# v0_2_4ch.net
KiCad netlist of a schematic drawn in EAGLE
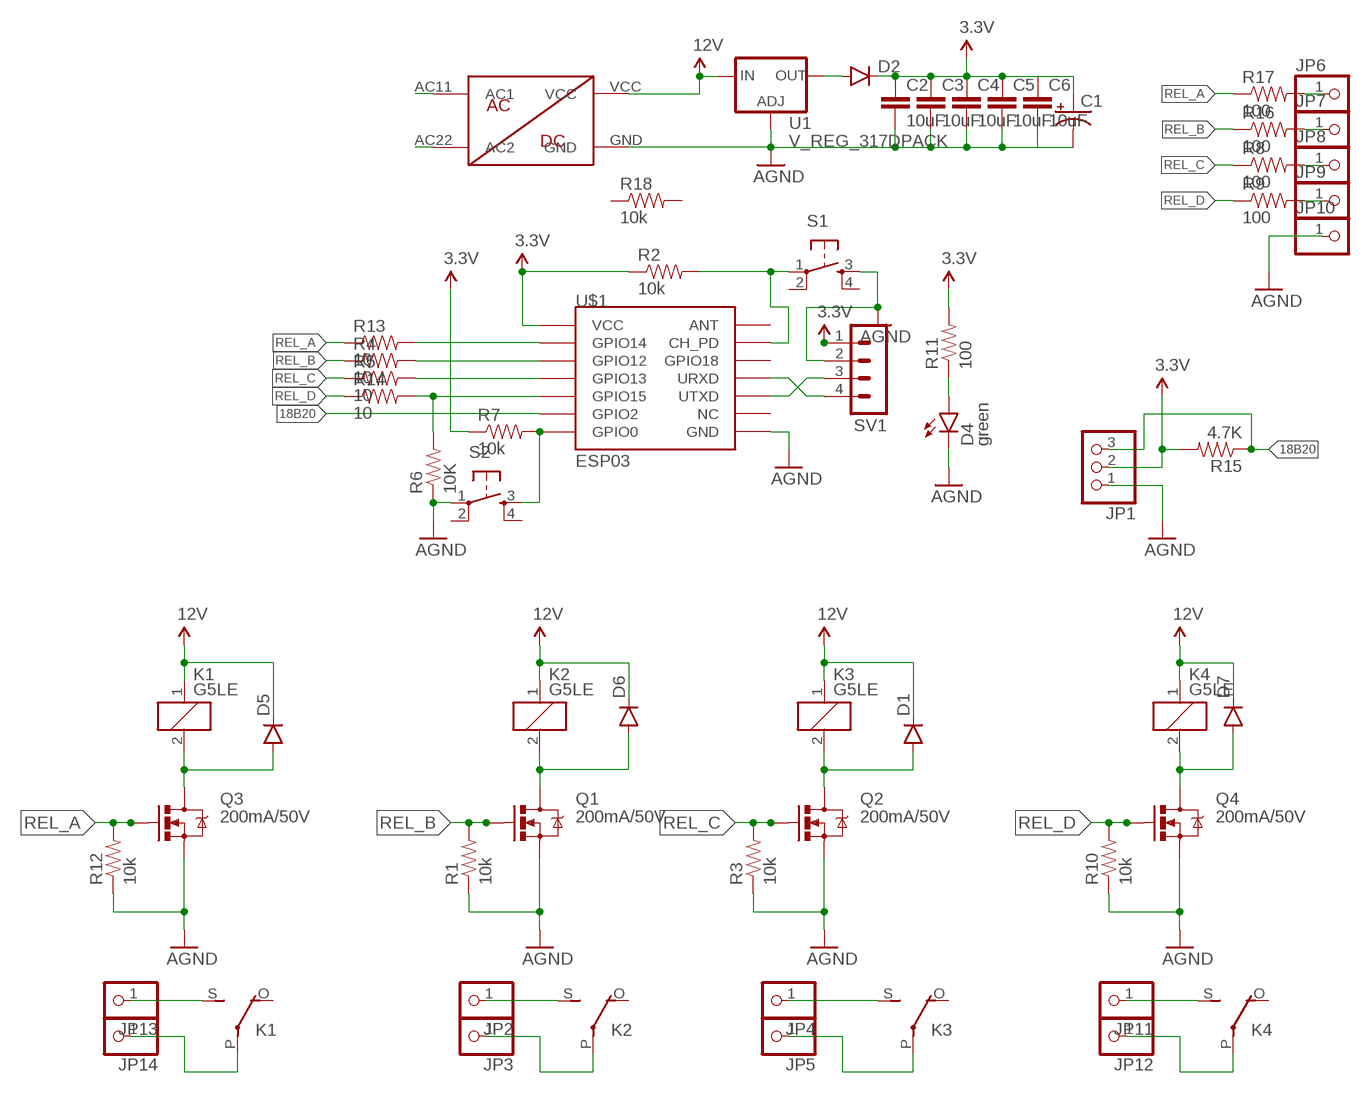
[diagram p0: schematic, sheet 1]

(export (version "E")
  (design (tool "Eeschema 10.0.6"))
  (components
    (comp (ref "C1")
      (value "CAP_POLPTH3")
      (footprint "eagle-import:CPOL-RADIAL-1000UF-63V")
      (libsource (lib "eagle-import") (part "CAP_POLPTH3"))
    )
    (comp (ref "C2")
      (value "10uF")
      (footprint "eagle-import:0603-CAP")
      (libsource (lib "eagle-import") (part "10UF-6.3V-20%(0603)"))
    )
    (comp (ref "C3")
      (value "10uF")
      (footprint "eagle-import:0603-CAP")
      (libsource (lib "eagle-import") (part "10UF-6.3V-20%(0603)"))
    )
    (comp (ref "C4")
      (value "10uF")
      (footprint "eagle-import:0603-CAP")
      (libsource (lib "eagle-import") (part "10UF-6.3V-20%(0603)"))
    )
    (comp (ref "C5")
      (value "10uF")
      (footprint "eagle-import:0603-CAP")
      (libsource (lib "eagle-import") (part "10UF-6.3V-20%(0603)"))
    )
    (comp (ref "C6")
      (value "10uF")
      (footprint "eagle-import:0603-CAP")
      (libsource (lib "eagle-import") (part "10UF-6.3V-20%(0603)"))
    )
    (comp (ref "D1")
      (value "DIODESOD123")
      (footprint "eagle-import:SOD-123")
      (libsource (lib "eagle-import") (part "DIODESOD123"))
    )
    (comp (ref "D2")
      (value "DIODESOD123")
      (footprint "eagle-import:SOD-123")
      (libsource (lib "eagle-import") (part "DIODESOD123"))
    )
    (comp (ref "D4")
      (value "green")
      (footprint "eagle-import:LED-0603")
      (libsource (lib "eagle-import") (part "LED0603"))
    )
    (comp (ref "D5")
      (value "DIODESOD123")
      (footprint "eagle-import:SOD-123")
      (libsource (lib "eagle-import") (part "DIODESOD123"))
    )
    (comp (ref "D6")
      (value "DIODESOD123")
      (footprint "eagle-import:SOD-123")
      (libsource (lib "eagle-import") (part "DIODESOD123"))
    )
    (comp (ref "D7")
      (value "DIODESOD123")
      (footprint "eagle-import:SOD-123")
      (libsource (lib "eagle-import") (part "DIODESOD123"))
    )
    (comp (ref "JP1")
      (value "PINHD-1X3")
      (footprint "eagle-import:1X03")
      (libsource (lib "eagle-import") (part "PINHD-1X3"))
    )
    (comp (ref "JP2")
      (value "PINHD-1X1")
      (footprint "eagle-import:1X01")
      (libsource (lib "eagle-import") (part "PINHD-1X1"))
    )
    (comp (ref "JP3")
      (value "PINHD-1X1")
      (footprint "eagle-import:1X01")
      (libsource (lib "eagle-import") (part "PINHD-1X1"))
    )
    (comp (ref "JP4")
      (value "PINHD-1X1")
      (footprint "eagle-import:1X01")
      (libsource (lib "eagle-import") (part "PINHD-1X1"))
    )
    (comp (ref "JP5")
      (value "PINHD-1X1")
      (footprint "eagle-import:1X01")
      (libsource (lib "eagle-import") (part "PINHD-1X1"))
    )
    (comp (ref "JP6")
      (value "PINHD-1X1")
      (footprint "eagle-import:1X01")
      (libsource (lib "eagle-import") (part "PINHD-1X1"))
    )
    (comp (ref "JP7")
      (value "PINHD-1X1")
      (footprint "eagle-import:1X01")
      (libsource (lib "eagle-import") (part "PINHD-1X1"))
    )
    (comp (ref "JP8")
      (value "PINHD-1X1")
      (footprint "eagle-import:1X01")
      (libsource (lib "eagle-import") (part "PINHD-1X1"))
    )
    (comp (ref "JP9")
      (value "PINHD-1X1")
      (footprint "eagle-import:1X01")
      (libsource (lib "eagle-import") (part "PINHD-1X1"))
    )
    (comp (ref "JP10")
      (value "PINHD-1X1")
      (footprint "eagle-import:1X01")
      (libsource (lib "eagle-import") (part "PINHD-1X1"))
    )
    (comp (ref "JP11")
      (value "PINHD-1X1")
      (footprint "eagle-import:1X01")
      (libsource (lib "eagle-import") (part "PINHD-1X1"))
    )
    (comp (ref "JP12")
      (value "PINHD-1X1")
      (footprint "eagle-import:1X01")
      (libsource (lib "eagle-import") (part "PINHD-1X1"))
    )
    (comp (ref "JP13")
      (value "PINHD-1X1")
      (footprint "eagle-import:1X01")
      (libsource (lib "eagle-import") (part "PINHD-1X1"))
    )
    (comp (ref "JP14")
      (value "PINHD-1X1")
      (footprint "eagle-import:1X01")
      (libsource (lib "eagle-import") (part "PINHD-1X1"))
    )
    (comp (ref "K1")
      (value "G5LE")
      (footprint "eagle-import:G5LE")
      (libsource (lib "eagle-import") (part "G5LE"))
    )
    (comp (ref "K2")
      (value "G5LE")
      (footprint "eagle-import:G5LE")
      (libsource (lib "eagle-import") (part "G5LE"))
    )
    (comp (ref "K3")
      (value "G5LE")
      (footprint "eagle-import:G5LE")
      (libsource (lib "eagle-import") (part "G5LE"))
    )
    (comp (ref "K4")
      (value "G5LE")
      (footprint "eagle-import:G5LE")
      (libsource (lib "eagle-import") (part "G5LE"))
    )
    (comp (ref "Q1")
      (value "200mA/50V")
      (footprint "eagle-import:SOT23-3")
      (libsource (lib "eagle-import") (part "MOSFET-NCHANNELBSS138"))
    )
    (comp (ref "Q2")
      (value "200mA/50V")
      (footprint "eagle-import:SOT23-3")
      (libsource (lib "eagle-import") (part "MOSFET-NCHANNELBSS138"))
    )
    (comp (ref "Q3")
      (value "200mA/50V")
      (footprint "eagle-import:SOT23-3")
      (libsource (lib "eagle-import") (part "MOSFET-NCHANNELBSS138"))
    )
    (comp (ref "Q4")
      (value "200mA/50V")
      (footprint "eagle-import:SOT23-3")
      (libsource (lib "eagle-import") (part "MOSFET-NCHANNELBSS138"))
    )
    (comp (ref "R1")
      (value "10k")
      (footprint "eagle-import:0805")
      (libsource (lib "eagle-import") (part "RESISTOR0805-RES"))
    )
    (comp (ref "R2")
      (value "10k")
      (footprint "eagle-import:0805")
      (libsource (lib "eagle-import") (part "RESISTOR0805-RES"))
    )
    (comp (ref "R3")
      (value "10k")
      (footprint "eagle-import:0805")
      (libsource (lib "eagle-import") (part "RESISTOR0805-RES"))
    )
    (comp (ref "R4")
      (value "10")
      (footprint "eagle-import:0805")
      (libsource (lib "eagle-import") (part "RESISTOR0805-RES"))
    )
    (comp (ref "R5")
      (value "10")
      (footprint "eagle-import:0805")
      (libsource (lib "eagle-import") (part "RESISTOR0805-RES"))
    )
    (comp (ref "R6")
      (value "10K")
      (footprint "eagle-import:0805")
      (libsource (lib "eagle-import") (part "RESISTOR0805-RES"))
    )
    (comp (ref "R7")
      (value "10k")
      (footprint "eagle-import:0805")
      (libsource (lib "eagle-import") (part "RESISTOR0805-RES"))
    )
    (comp (ref "R8")
      (value "100")
      (footprint "eagle-import:0805")
      (libsource (lib "eagle-import") (part "RESISTOR0805-RES"))
    )
    (comp (ref "R9")
      (value "100")
      (footprint "eagle-import:0805")
      (libsource (lib "eagle-import") (part "RESISTOR0805-RES"))
    )
    (comp (ref "R10")
      (value "10k")
      (footprint "eagle-import:0805")
      (libsource (lib "eagle-import") (part "RESISTOR0805-RES"))
    )
    (comp (ref "R11")
      (value "100")
      (footprint "eagle-import:0805")
      (libsource (lib "eagle-import") (part "RESISTOR0805-RES"))
    )
    (comp (ref "R12")
      (value "10k")
      (footprint "eagle-import:0805")
      (libsource (lib "eagle-import") (part "RESISTOR0805-RES"))
    )
    (comp (ref "R13")
      (value "10")
      (footprint "eagle-import:0805")
      (libsource (lib "eagle-import") (part "RESISTOR0805-RES"))
    )
    (comp (ref "R14")
      (value "10")
      (footprint "eagle-import:0805")
      (libsource (lib "eagle-import") (part "RESISTOR0805-RES"))
    )
    (comp (ref "R15")
      (value "4.7K")
      (footprint "eagle-import:0805")
      (libsource (lib "eagle-import") (part "RESISTOR0805-RES"))
    )
    (comp (ref "R16")
      (value "100")
      (footprint "eagle-import:0805")
      (libsource (lib "eagle-import") (part "RESISTOR0805-RES"))
    )
    (comp (ref "R17")
      (value "100")
      (footprint "eagle-import:0805")
      (libsource (lib "eagle-import") (part "RESISTOR0805-RES"))
    )
    (comp (ref "R18")
      (value "10k")
      (footprint "eagle-import:0805")
      (libsource (lib "eagle-import") (part "RESISTOR0805-RES"))
    )
    (comp (ref "S1")
      (value "TAC_SWITCHPTH")
      (footprint "eagle-import:TACTILE-PTH")
      (libsource (lib "eagle-import") (part "TAC_SWITCHPTH"))
    )
    (comp (ref "S2")
      (value "TAC_SWITCHPTH")
      (footprint "eagle-import:TACTILE-PTH")
      (libsource (lib "eagle-import") (part "TAC_SWITCHPTH"))
    )
    (comp (ref "SV1")
      (value "MA04-1")
      (footprint "eagle-import:MA04-1")
      (libsource (lib "eagle-import") (part "MA04-1"))
    )
    (comp (ref "U$1")
      (value "ESP03")
      (footprint "eagle-import:ESP03")
      (libsource (lib "eagle-import") (part "ESP03"))
    )
    (comp (ref "U$8")
      (value "ACDC12V350MA")
      (footprint "eagle-import:ACDC12V350MA")
      (libsource (lib "eagle-import") (part "ACDC12V350MA"))
    )
    (comp (ref "U1")
      (value "V_REG_317DPACK")
      (footprint "eagle-import:V-REG_DPACK")
      (libsource (lib "eagle-import") (part "V_REG_317DPACK"))
    )
  )
  (nets
    (net (code "1") (name "3.3V") (class "Default")
      (node (ref "C1") (pin "1") (pinfunction "+_1") (pintype "passive"))
      (node (ref "C2") (pin "1") (pinfunction "1_1") (pintype "passive"))
      (node (ref "C3") (pin "1") (pinfunction "1_1") (pintype "passive"))
      (node (ref "C4") (pin "1") (pinfunction "1_1") (pintype "passive"))
      (node (ref "C5") (pin "1") (pinfunction "1_1") (pintype "passive"))
      (node (ref "C6") (pin "1") (pinfunction "1_1") (pintype "passive"))
      (node (ref "D2") (pin "C") (pinfunction "C_C") (pintype "passive"))
      (node (ref "JP1") (pin "2") (pinfunction "2_2") (pintype "passive"))
      (node (ref "R11") (pin "2") (pinfunction "2_2") (pintype "passive"))
      (node (ref "R15") (pin "2") (pinfunction "2_2") (pintype "passive"))
      (node (ref "R2") (pin "1") (pinfunction "1_1") (pintype "passive"))
      (node (ref "R7") (pin "1") (pinfunction "1_1") (pintype "passive"))
      (node (ref "SV1") (pin "1") (pinfunction "1_1") (pintype "passive"))
      (node (ref "U$1") (pin "VCC") (pinfunction "VCC_VCC") (pintype "bidirectional"))
    )
    (net (code "2") (name "12V") (class "Default")
      (node (ref "D1") (pin "C") (pinfunction "C_C") (pintype "passive"))
      (node (ref "D5") (pin "C") (pinfunction "C_C") (pintype "passive"))
      (node (ref "D6") (pin "C") (pinfunction "C_C") (pintype "passive"))
      (node (ref "D7") (pin "C") (pinfunction "C_C") (pintype "passive"))
      (node (ref "K1") (pin "1") (pinfunction "1_1") (pintype "passive"))
      (node (ref "K2") (pin "1") (pinfunction "1_1") (pintype "passive"))
      (node (ref "K3") (pin "1") (pinfunction "1_1") (pintype "passive"))
      (node (ref "K4") (pin "1") (pinfunction "1_1") (pintype "passive"))
      (node (ref "U$8") (pin "VCC") (pinfunction "VCC_VCC") (pintype "bidirectional"))
      (node (ref "U1") (pin "3") (pinfunction "IN_3") (pintype "input"))
    )
    (net (code "3") (name "18B20") (class "Default")
      (node (ref "JP1") (pin "3") (pinfunction "3_3") (pintype "passive"))
      (node (ref "R15") (pin "1") (pinfunction "1_1") (pintype "passive"))
      (node (ref "U$1") (pin "GPIO2") (pinfunction "GPIO2_GPIO2") (pintype "bidirectional"))
    )
    (net (code "4") (name "AGND") (class "Default")
      (node (ref "C1") (pin "2") (pinfunction "-_2") (pintype "passive"))
      (node (ref "C2") (pin "2") (pinfunction "2_2") (pintype "passive"))
      (node (ref "C3") (pin "2") (pinfunction "2_2") (pintype "passive"))
      (node (ref "C4") (pin "2") (pinfunction "2_2") (pintype "passive"))
      (node (ref "C5") (pin "2") (pinfunction "2_2") (pintype "passive"))
      (node (ref "C6") (pin "2") (pinfunction "2_2") (pintype "passive"))
      (node (ref "D4") (pin "C") (pinfunction "C_C") (pintype "passive"))
      (node (ref "JP1") (pin "1") (pinfunction "1_1") (pintype "passive"))
      (node (ref "JP10") (pin "1") (pinfunction "1_1") (pintype "passive"))
      (node (ref "Q1") (pin "2") (pinfunction "S_2") (pintype "passive"))
      (node (ref "Q2") (pin "2") (pinfunction "S_2") (pintype "passive"))
      (node (ref "Q3") (pin "2") (pinfunction "S_2") (pintype "passive"))
      (node (ref "Q4") (pin "2") (pinfunction "S_2") (pintype "passive"))
      (node (ref "R1") (pin "1") (pinfunction "1_1") (pintype "passive"))
      (node (ref "R10") (pin "1") (pinfunction "1_1") (pintype "passive"))
      (node (ref "R12") (pin "1") (pinfunction "1_1") (pintype "passive"))
      (node (ref "R3") (pin "1") (pinfunction "1_1") (pintype "passive"))
      (node (ref "R6") (pin "1") (pinfunction "1_1") (pintype "passive"))
      (node (ref "S1") (pin "3") (pinfunction "3_3") (pintype "passive"))
      (node (ref "S2") (pin "1") (pinfunction "1_1") (pintype "passive"))
      (node (ref "SV1") (pin "2") (pinfunction "2_2") (pintype "passive"))
      (node (ref "U$1") (pin "GND") (pinfunction "GND_GND") (pintype "bidirectional"))
      (node (ref "U$8") (pin "GND") (pinfunction "GND_GND") (pintype "bidirectional"))
      (node (ref "U1") (pin "1") (pinfunction "ADJ_1") (pintype "input"))
    )
    (net (code "5") (name "Net-(D4-PadA)") (class "Default")
      (node (ref "D4") (pin "A") (pinfunction "A_A") (pintype "passive"))
      (node (ref "R11") (pin "1") (pinfunction "1_1") (pintype "passive"))
    )
    (net (code "6") (name "Net-(JP2-Pad1)") (class "Default")
      (node (ref "JP2") (pin "1") (pinfunction "1_1") (pintype "passive"))
      (node (ref "K2") (pin "S") (pinfunction "S_S") (pintype "passive"))
    )
    (net (code "7") (name "Net-(JP3-Pad1)") (class "Default")
      (node (ref "JP3") (pin "1") (pinfunction "1_1") (pintype "passive"))
      (node (ref "K2") (pin "P") (pinfunction "P_P") (pintype "passive"))
    )
    (net (code "8") (name "Net-(JP4-Pad1)") (class "Default")
      (node (ref "JP4") (pin "1") (pinfunction "1_1") (pintype "passive"))
      (node (ref "K3") (pin "S") (pinfunction "S_S") (pintype "passive"))
    )
    (net (code "9") (name "Net-(JP5-Pad1)") (class "Default")
      (node (ref "JP5") (pin "1") (pinfunction "1_1") (pintype "passive"))
      (node (ref "K3") (pin "P") (pinfunction "P_P") (pintype "passive"))
    )
    (net (code "10") (name "Net-(JP6-Pad1)") (class "Default")
      (node (ref "JP6") (pin "1") (pinfunction "1_1") (pintype "passive"))
      (node (ref "R17") (pin "2") (pinfunction "2_2") (pintype "passive"))
    )
    (net (code "11") (name "Net-(JP7-Pad1)") (class "Default")
      (node (ref "JP7") (pin "1") (pinfunction "1_1") (pintype "passive"))
      (node (ref "R16") (pin "2") (pinfunction "2_2") (pintype "passive"))
    )
    (net (code "12") (name "Net-(JP8-Pad1)") (class "Default")
      (node (ref "JP8") (pin "1") (pinfunction "1_1") (pintype "passive"))
      (node (ref "R8") (pin "2") (pinfunction "2_2") (pintype "passive"))
    )
    (net (code "13") (name "Net-(JP9-Pad1)") (class "Default")
      (node (ref "JP9") (pin "1") (pinfunction "1_1") (pintype "passive"))
      (node (ref "R9") (pin "2") (pinfunction "2_2") (pintype "passive"))
    )
    (net (code "14") (name "Net-(JP11-Pad1)") (class "Default")
      (node (ref "JP11") (pin "1") (pinfunction "1_1") (pintype "passive"))
      (node (ref "K4") (pin "S") (pinfunction "S_S") (pintype "passive"))
    )
    (net (code "15") (name "Net-(JP12-Pad1)") (class "Default")
      (node (ref "JP12") (pin "1") (pinfunction "1_1") (pintype "passive"))
      (node (ref "K4") (pin "P") (pinfunction "P_P") (pintype "passive"))
    )
    (net (code "16") (name "Net-(JP13-Pad1)") (class "Default")
      (node (ref "JP13") (pin "1") (pinfunction "1_1") (pintype "passive"))
      (node (ref "K1") (pin "S") (pinfunction "S_S") (pintype "passive"))
    )
    (net (code "17") (name "Net-(JP14-Pad1)") (class "Default")
      (node (ref "JP14") (pin "1") (pinfunction "1_1") (pintype "passive"))
      (node (ref "K1") (pin "P") (pinfunction "P_P") (pintype "passive"))
    )
    (net (code "18") (name "Net-(Q1-D)") (class "Default")
      (node (ref "D6") (pin "A") (pinfunction "A_A") (pintype "passive"))
      (node (ref "K2") (pin "2") (pinfunction "2_2") (pintype "passive"))
      (node (ref "Q1") (pin "3") (pinfunction "D_3") (pintype "passive"))
    )
    (net (code "19") (name "Net-(Q2-D)") (class "Default")
      (node (ref "D1") (pin "A") (pinfunction "A_A") (pintype "passive"))
      (node (ref "K3") (pin "2") (pinfunction "2_2") (pintype "passive"))
      (node (ref "Q2") (pin "3") (pinfunction "D_3") (pintype "passive"))
    )
    (net (code "20") (name "Net-(Q3-D)") (class "Default")
      (node (ref "D5") (pin "A") (pinfunction "A_A") (pintype "passive"))
      (node (ref "K1") (pin "2") (pinfunction "2_2") (pintype "passive"))
      (node (ref "Q3") (pin "3") (pinfunction "D_3") (pintype "passive"))
    )
    (net (code "21") (name "Net-(Q4-D)") (class "Default")
      (node (ref "D7") (pin "A") (pinfunction "A_A") (pintype "passive"))
      (node (ref "K4") (pin "2") (pinfunction "2_2") (pintype "passive"))
      (node (ref "Q4") (pin "3") (pinfunction "D_3") (pintype "passive"))
    )
    (net (code "22") (name "Net-(R2-Pad2)") (class "Default")
      (node (ref "R2") (pin "2") (pinfunction "2_2") (pintype "passive"))
      (node (ref "S1") (pin "1") (pinfunction "1_1") (pintype "passive"))
      (node (ref "U$1") (pin "CH_PD") (pinfunction "CH_PD_CH_PD") (pintype "bidirectional"))
    )
    (net (code "23") (name "Net-(R4-Pad2)") (class "Default")
      (node (ref "R4") (pin "2") (pinfunction "2_2") (pintype "passive"))
      (node (ref "U$1") (pin "GPIO12") (pinfunction "GPIO12_GPIO12") (pintype "bidirectional"))
    )
    (net (code "24") (name "Net-(R5-Pad2)") (class "Default")
      (node (ref "R5") (pin "2") (pinfunction "2_2") (pintype "passive"))
      (node (ref "U$1") (pin "GPIO13") (pinfunction "GPIO13_GPIO13") (pintype "bidirectional"))
    )
    (net (code "25") (name "Net-(R7-Pad2)") (class "Default")
      (node (ref "R7") (pin "2") (pinfunction "2_2") (pintype "passive"))
      (node (ref "S2") (pin "3") (pinfunction "3_3") (pintype "passive"))
      (node (ref "U$1") (pin "GPIO0") (pinfunction "GPIO0_GPIO0") (pintype "bidirectional"))
    )
    (net (code "26") (name "Net-(R13-Pad2)") (class "Default")
      (node (ref "R13") (pin "2") (pinfunction "2_2") (pintype "passive"))
      (node (ref "U$1") (pin "GPIO14") (pinfunction "GPIO14_GPIO14") (pintype "bidirectional"))
    )
    (net (code "27") (name "Net-(R14-Pad2)") (class "Default")
      (node (ref "R14") (pin "2") (pinfunction "2_2") (pintype "passive"))
      (node (ref "R6") (pin "2") (pinfunction "2_2") (pintype "passive"))
      (node (ref "U$1") (pin "GPIO15") (pinfunction "GPIO15_GPIO15") (pintype "bidirectional"))
    )
    (net (code "28") (name "Net-(SV1-Pad3)") (class "Default")
      (node (ref "SV1") (pin "3") (pinfunction "3_3") (pintype "passive"))
      (node (ref "U$1") (pin "UTXD") (pinfunction "UTXD_UTXD") (pintype "bidirectional"))
    )
    (net (code "29") (name "Net-(SV1-Pad4)") (class "Default")
      (node (ref "SV1") (pin "4") (pinfunction "4_4") (pintype "passive"))
      (node (ref "U$1") (pin "URXD") (pinfunction "URXD_URXD") (pintype "bidirectional"))
    )
    (net (code "30") (name "Net-(U1-OUT)") (class "Default")
      (node (ref "D2") (pin "A") (pinfunction "A_A") (pintype "passive"))
      (node (ref "U1") (pin "4") (pinfunction "OUT_4") (pintype "output"))
    )
    (net (code "31") (name "REL_A") (class "Default")
      (node (ref "Q3") (pin "1") (pinfunction "G_1") (pintype "passive"))
      (node (ref "R12") (pin "2") (pinfunction "2_2") (pintype "passive"))
      (node (ref "R13") (pin "1") (pinfunction "1_1") (pintype "passive"))
      (node (ref "R17") (pin "1") (pinfunction "1_1") (pintype "passive"))
    )
    (net (code "32") (name "REL_B") (class "Default")
      (node (ref "Q1") (pin "1") (pinfunction "G_1") (pintype "passive"))
      (node (ref "R1") (pin "2") (pinfunction "2_2") (pintype "passive"))
      (node (ref "R16") (pin "1") (pinfunction "1_1") (pintype "passive"))
      (node (ref "R4") (pin "1") (pinfunction "1_1") (pintype "passive"))
    )
    (net (code "33") (name "REL_C") (class "Default")
      (node (ref "Q2") (pin "1") (pinfunction "G_1") (pintype "passive"))
      (node (ref "R3") (pin "2") (pinfunction "2_2") (pintype "passive"))
      (node (ref "R5") (pin "1") (pinfunction "1_1") (pintype "passive"))
      (node (ref "R8") (pin "1") (pinfunction "1_1") (pintype "passive"))
    )
    (net (code "34") (name "REL_D") (class "Default")
      (node (ref "Q4") (pin "1") (pinfunction "G_1") (pintype "passive"))
      (node (ref "R10") (pin "2") (pinfunction "2_2") (pintype "passive"))
      (node (ref "R14") (pin "1") (pinfunction "1_1") (pintype "passive"))
      (node (ref "R9") (pin "1") (pinfunction "1_1") (pintype "passive"))
    )
    (net (code "35") (name "unconnected-(K1-PadO)") (class "Default")
      (node (ref "K1") (pin "O") (pinfunction "O_O") (pintype "passive"))
    )
    (net (code "36") (name "unconnected-(K2-PadO)") (class "Default")
      (node (ref "K2") (pin "O") (pinfunction "O_O") (pintype "passive"))
    )
    (net (code "37") (name "unconnected-(K3-PadO)") (class "Default")
      (node (ref "K3") (pin "O") (pinfunction "O_O") (pintype "passive"))
    )
    (net (code "38") (name "unconnected-(K4-PadO)") (class "Default")
      (node (ref "K4") (pin "O") (pinfunction "O_O") (pintype "passive"))
    )
    (net (code "39") (name "unconnected-(R18-Pad1)") (class "Default")
      (node (ref "R18") (pin "1") (pinfunction "1_1") (pintype "passive"))
    )
    (net (code "40") (name "unconnected-(R18-Pad2)") (class "Default")
      (node (ref "R18") (pin "2") (pinfunction "2_2") (pintype "passive"))
    )
    (net (code "41") (name "unconnected-(S1-Pad2)") (class "Default")
      (node (ref "S1") (pin "2") (pinfunction "2_2") (pintype "passive"))
    )
    (net (code "42") (name "unconnected-(S1-Pad4)") (class "Default")
      (node (ref "S1") (pin "4") (pinfunction "4_4") (pintype "passive"))
    )
    (net (code "43") (name "unconnected-(S2-Pad2)") (class "Default")
      (node (ref "S2") (pin "2") (pinfunction "2_2") (pintype "passive"))
    )
    (net (code "44") (name "unconnected-(S2-Pad4)") (class "Default")
      (node (ref "S2") (pin "4") (pinfunction "4_4") (pintype "passive"))
    )
    (net (code "45") (name "unconnected-(U$1-PadANT)") (class "Default")
      (node (ref "U$1") (pin "ANT") (pinfunction "ANT_ANT") (pintype "bidirectional"))
    )
    (net (code "46") (name "unconnected-(U$1-PadGPIO18)") (class "Default")
      (node (ref "U$1") (pin "GPIO18") (pinfunction "GPIO18_GPIO18") (pintype "bidirectional"))
    )
    (net (code "47") (name "unconnected-(U$1-PadNC)") (class "Default")
      (node (ref "U$1") (pin "NC") (pinfunction "NC_NC") (pintype "bidirectional"))
    )
    (net (code "48") (name "unconnected-(U$8-AC1-PadAC11)") (class "Default")
      (node (ref "U$8") (pin "AC11") (pinfunction "AC1_AC11") (pintype "bidirectional"))
    )
    (net (code "49") (name "unconnected-(U$8-AC2-PadAC22)") (class "Default")
      (node (ref "U$8") (pin "AC22") (pinfunction "AC2_AC22") (pintype "bidirectional"))
    )
  )
)
